# SparkFun_Fuse_Breakout_Board.net
KiCad netlist of a schematic drawn in EAGLE
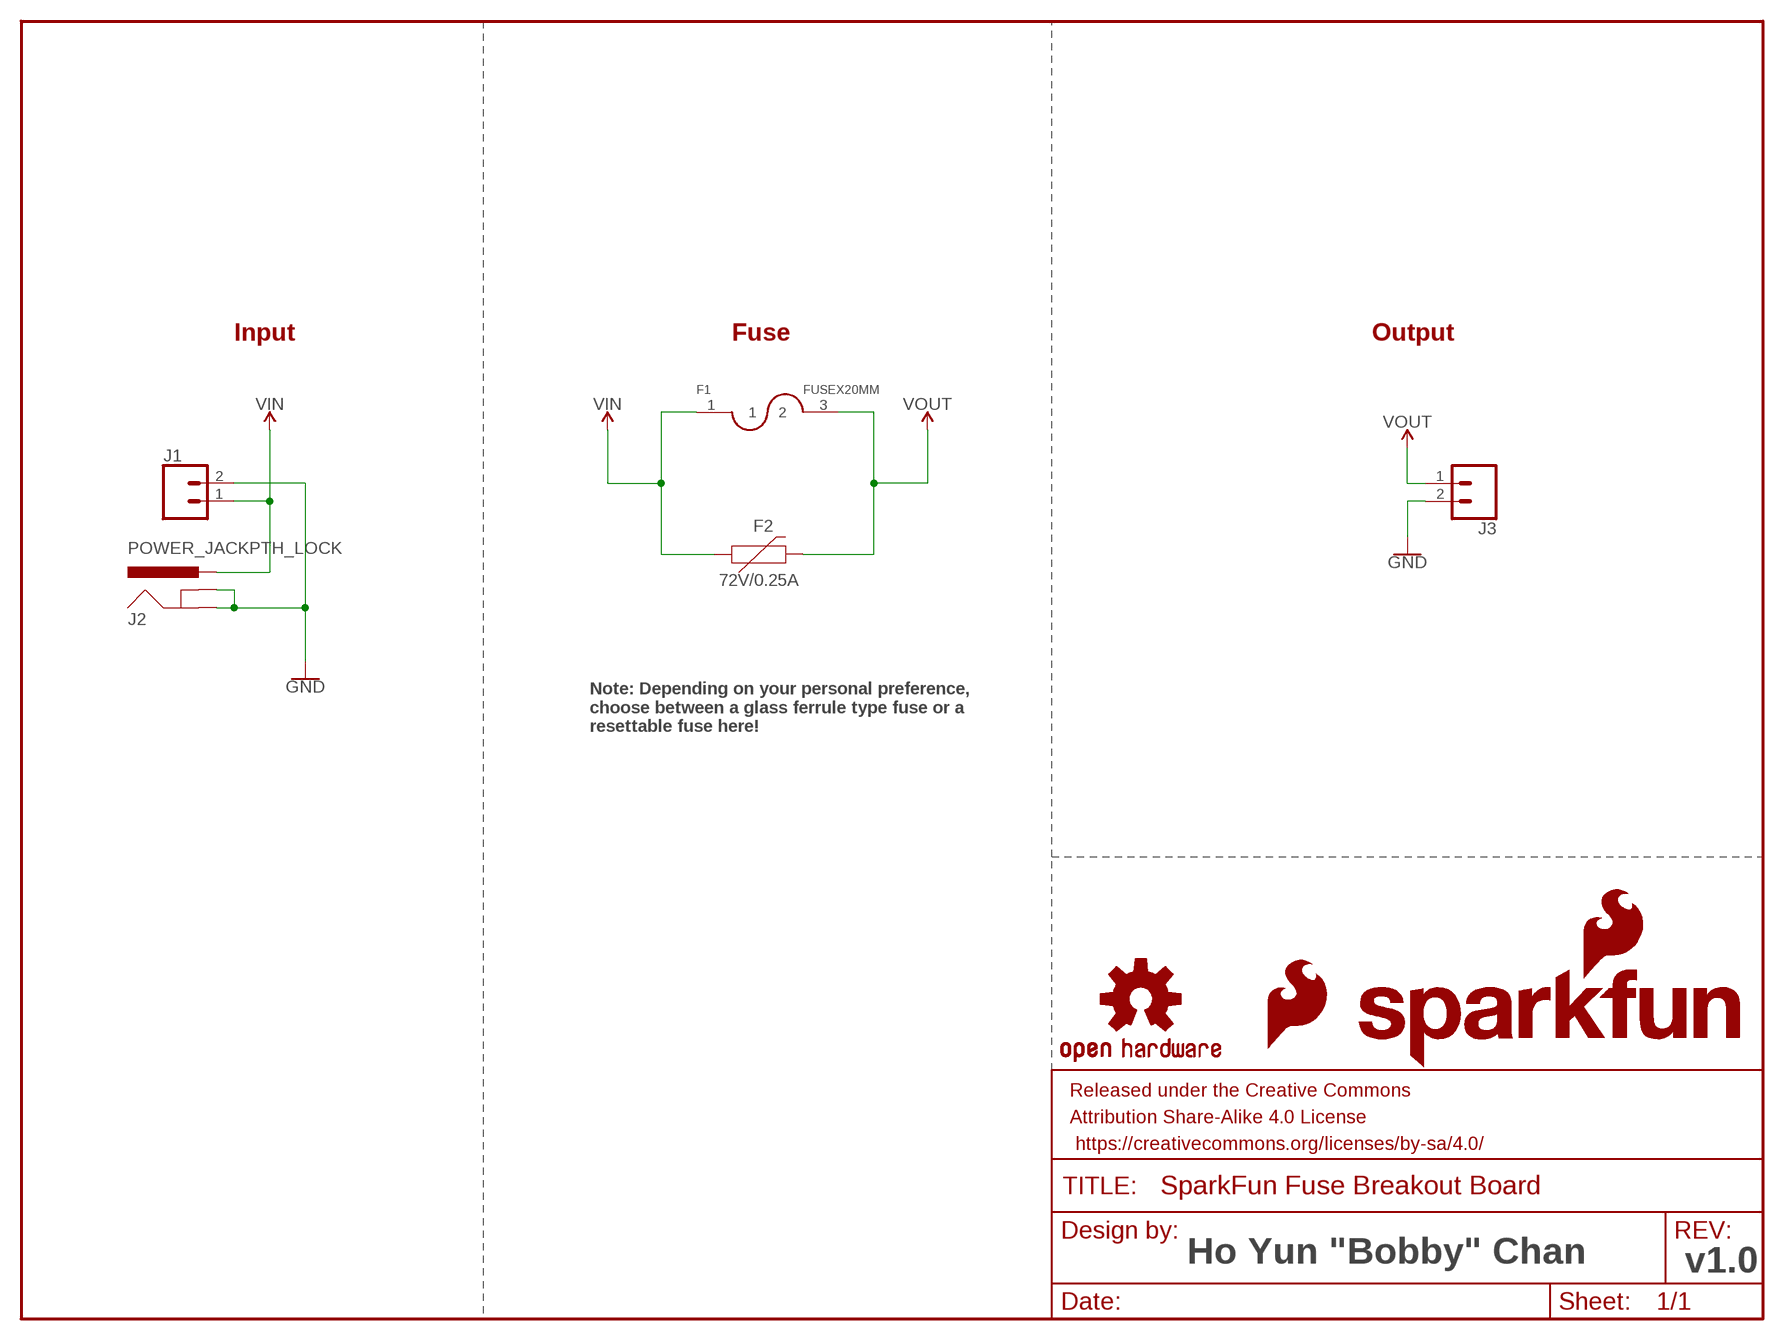
[diagram p0: schematic, sheet 1]

(export (version "E")
  (design (tool "Eeschema 10.0.6"))
  (components
    (comp (ref "F1")
      (value "FUSEX20MM")
      (footprint "eagle-import:FUSE_5MM")
      (libsource (lib "eagle-import") (part "FUSEX20MM"))
    )
    (comp (ref "F2")
      (value "72V/0.25A")
      (footprint "eagle-import:PTH")
      (libsource (lib "eagle-import") (part "PPTC_PTH"))
    )
    (comp (ref "FRAME1")
      (value "FRAME-LETTER")
      (footprint "eagle-import:CREATIVE_COMMONS")
      (libsource (lib "eagle-import") (part "FRAME-LETTER"))
    )
    (comp (ref "J1")
      (value "CONN_025MM")
      (footprint "eagle-import:SCREWTERMINAL-5MM-2")
      (libsource (lib "eagle-import") (part "CONN_025MM"))
    )
    (comp (ref "J2")
      (value "POWER_JACKPTH_LOCK")
      (footprint "eagle-import:POWER_JACK_PTH_LOCK")
      (libsource (lib "eagle-import") (part "POWER_JACKPTH_LOCK"))
    )
    (comp (ref "J3")
      (value "CONN_025MM")
      (footprint "eagle-import:SCREWTERMINAL-5MM-2")
      (libsource (lib "eagle-import") (part "CONN_025MM"))
    )
    (comp (ref "LOGO1")
      (value "SFE_LOGO_NAME_FLAME.1_INCH")
      (footprint "eagle-import:SFE_LOGO_NAME_FLAME_.1")
      (libsource (lib "eagle-import") (part "SFE_LOGO_NAME_FLAME.1_INCH"))
    )
    (comp (ref "LOGO2")
      (value "SFE_LOGO_FLAME.1_INCH")
      (footprint "eagle-import:SFE_LOGO_FLAME_.1")
      (libsource (lib "eagle-import") (part "SFE_LOGO_FLAME.1_INCH"))
    )
    (comp (ref "LOGO3")
      (value "OSHW-LOGOMINI")
      (footprint "eagle-import:OSHW-LOGO-MINI")
      (libsource (lib "eagle-import") (part "OSHW-LOGOMINI"))
    )
  )
  (nets
    (net (code "1") (name "GND") (class "Default")
      (node (ref "J1") (pin "2") (pinfunction "2_2") (pintype "passive"))
      (node (ref "J2") (pin "GND") (pinfunction "GND_GND") (pintype "bidirectional"))
      (node (ref "J2") (pin "GNDBREAK") (pinfunction "GNDBREAK_GNDBREAK") (pintype "bidirectional"))
      (node (ref "J3") (pin "2") (pinfunction "2_2") (pintype "passive"))
    )
    (net (code "2") (name "VIN") (class "Default")
      (node (ref "F1") (pin "1") (pinfunction "1_1") (pintype "bidirectional"))
      (node (ref "F2") (pin "P$1") (pinfunction "1_P$1") (pintype "bidirectional"))
      (node (ref "J1") (pin "1") (pinfunction "1_1") (pintype "passive"))
      (node (ref "J2") (pin "PWR") (pinfunction "PWR_PWR") (pintype "bidirectional"))
    )
    (net (code "3") (name "VOUT") (class "Default")
      (node (ref "F1") (pin "3") (pinfunction "2_3") (pintype "bidirectional"))
      (node (ref "F2") (pin "P$2") (pinfunction "2_P$2") (pintype "bidirectional"))
      (node (ref "J3") (pin "1") (pinfunction "1_1") (pintype "passive"))
    )
  )
)
